# Fake_ACS_Board_Schematic.net
KiCad netlist of a schematic drawn in Altium Designer
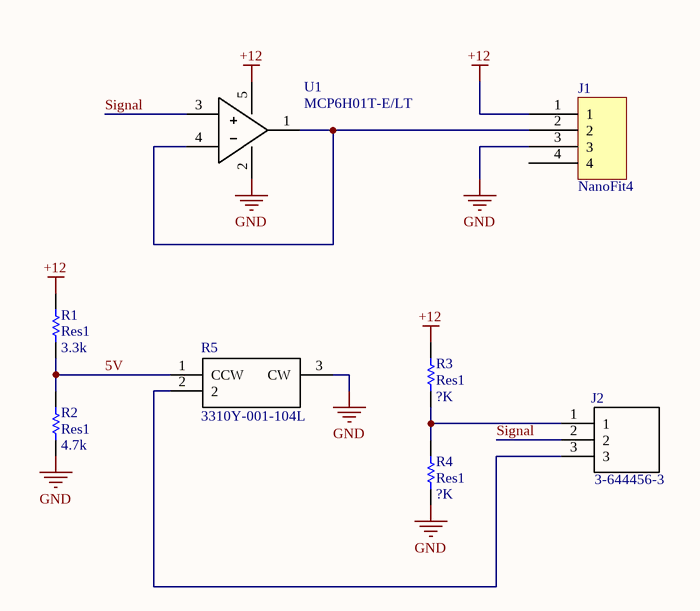
[diagram p0: Fake_ACS_Board_Schematic.SchDoc]

(export (version "E")
  (design (tool "Eeschema 10.0.6"))
  (components
    (comp (ref "J1")
      (value "NanoFit4")
      (footprint "Fake_ACS_Board_Footprints:1053141304")
      (libsource (lib "Fake_ACS_Board_Schematics") (part "NanoFit4"))
    )
    (comp (ref "J2")
      (value "3-644456-3")
      (footprint "Fake_ACS_Board_Footprints:*TE_3-644456-3")
      (libsource (lib "Fake_ACS_Board_Schematics") (part "3-644456-3"))
    )
    (comp (ref "R1")
      (value "Res1")
      (footprint "RESC1608X06N")
      (description "Resistor")
      (fields (field (name "ALTIUM_VALUE") "3.3k") (field (name "PUBLISHER") "Altium Limited"))
      (libsource (lib "Miscellaneous Devices") (part "Res1"))
    )
    (comp (ref "R2")
      (value "Res1")
      (footprint "RESC1608X06N")
      (description "Resistor")
      (fields (field (name "ALTIUM_VALUE") "4.7k") (field (name "PUBLISHER") "Altium Limited"))
      (libsource (lib "Miscellaneous Devices") (part "Res1"))
    )
    (comp (ref "R3")
      (value "Res1")
      (footprint "RESC1608X06N")
      (description "Resistor")
      (fields (field (name "ALTIUM_VALUE") "?K") (field (name "PUBLISHER") "Altium Limited"))
      (libsource (lib "Miscellaneous Devices") (part "Res1"))
    )
    (comp (ref "R4")
      (value "Res1")
      (footprint "RESC1608X06N")
      (description "Resistor")
      (fields (field (name "ALTIUM_VALUE") "?K") (field (name "PUBLISHER") "Altium Limited"))
      (libsource (lib "Miscellaneous Devices") (part "Res1"))
    )
    (comp (ref "R5")
      (value "3310Y-001-104L")
      (footprint "Fake_ACS_Board_Footprints:3310Y-001")
      (description "Resistor")
      (fields
        (field (name "MOUSER PART NUMBER") "652-3310Y-001-104L")
        (field (name "RS PART NUMBER") "2508317400")
      )
      (libsource (lib "Fake_ACS_Board_Schematics") (part "3310Y-001-104L"))
    )
    (comp (ref "U1")
      (value "MCP6H01T-E/LT")
      (footprint "SOT95P270X115-5N")
      (libsource (lib "Fake_ACS_Board_Schematics") (part "MCP6H01T-E/LT"))
    )
  )
  (nets
    (net (code "1") (name "+12") (class "Default")
      (node (ref "J1") (pin "1") (pinfunction "1_1") (pintype "passive"))
      (node (ref "R1") (pin "2") (pinfunction "2_2") (pintype "passive"))
      (node (ref "R3") (pin "2") (pinfunction "2_2") (pintype "passive"))
      (node (ref "U1") (pin "5") (pinfunction "VDD_5") (pintype "passive"))
    )
    (net (code "2") (name "/5V") (class "Default")
      (node (ref "R1") (pin "1") (pinfunction "1_1") (pintype "passive"))
      (node (ref "R2") (pin "2") (pinfunction "2_2") (pintype "passive"))
      (node (ref "R5") (pin "1") (pinfunction "CCW_1") (pintype "passive"))
    )
    (net (code "3") (name "/Signal") (class "Default")
      (node (ref "J2") (pin "2") (pinfunction "2_2") (pintype "passive"))
      (node (ref "U1") (pin "3") (pinfunction "IN1+_3") (pintype "passive"))
    )
    (net (code "4") (name "GND") (class "Default")
      (node (ref "J1") (pin "3") (pinfunction "3_3") (pintype "passive"))
      (node (ref "R2") (pin "1") (pinfunction "1_1") (pintype "passive"))
      (node (ref "R4") (pin "1") (pinfunction "1_1") (pintype "passive"))
      (node (ref "R5") (pin "3") (pinfunction "CW_3") (pintype "passive"))
      (node (ref "U1") (pin "2") (pinfunction "VSS_2") (pintype "passive"))
    )
    (net (code "5") (name "Net-(J2-Pad1)") (class "Default")
      (node (ref "J2") (pin "1") (pinfunction "1_1") (pintype "passive"))
      (node (ref "R3") (pin "1") (pinfunction "1_1") (pintype "passive"))
      (node (ref "R4") (pin "2") (pinfunction "2_2") (pintype "passive"))
    )
    (net (code "6") (name "Net-(J2-Pad3)") (class "Default")
      (node (ref "J2") (pin "3") (pinfunction "3_3") (pintype "passive"))
      (node (ref "R5") (pin "2") (pinfunction "2_2") (pintype "passive"))
    )
    (net (code "7") (name "Net-(U1-IN1-)") (class "Default")
      (node (ref "J1") (pin "2") (pinfunction "2_2") (pintype "passive"))
      (node (ref "U1") (pin "1") (pinfunction "VOUT_1") (pintype "passive"))
      (node (ref "U1") (pin "4") (pinfunction "IN1-_4") (pintype "passive"))
    )
    (net (code "8") (name "unconnected-(J1-Pad4)") (class "Default")
      (node (ref "J1") (pin "4") (pinfunction "4_4") (pintype "passive"))
    )
  )
)
